# MOTOR_DVR.net
KiCad netlist of a schematic drawn in Altium Designer
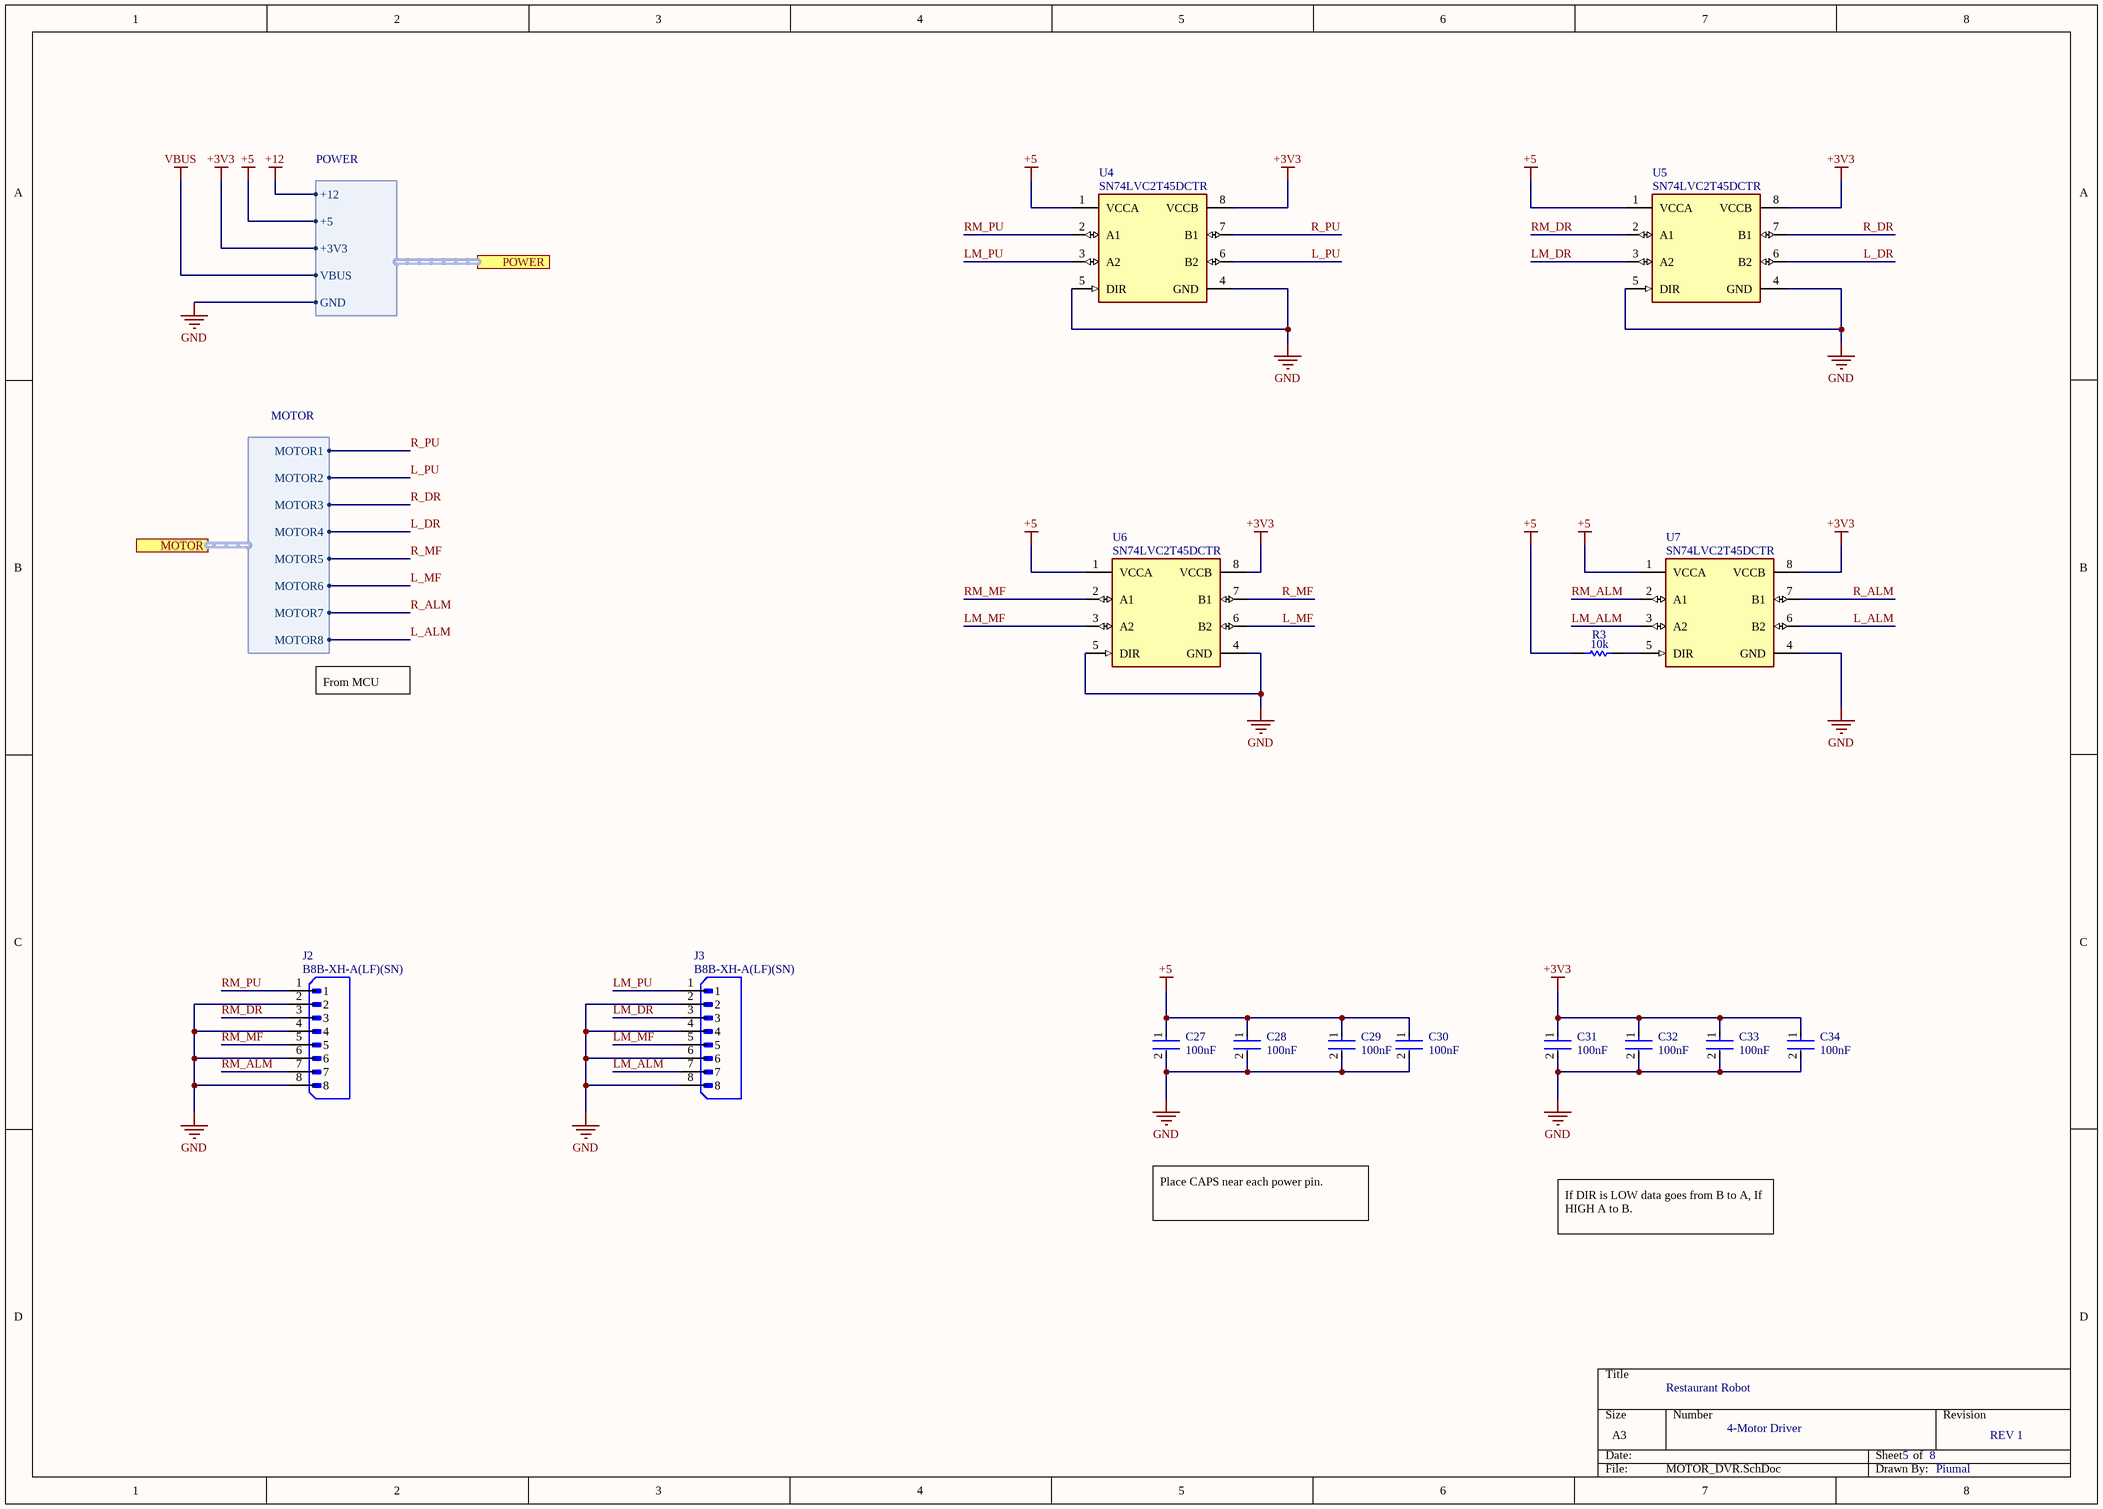
[diagram p0: MOTOR_DVR.SchDoc]

(export (version "E")
  (design (tool "Eeschema 10.0.6"))
  (components
    (comp (ref "C27")
      (value "CL21B104KOANNNC")
      (footprint "FP-CL21-IPC_A")
      (description "CL21 Series 0805 100nF 16V ±10% Tolerance X7R Multilayer Ceramic Chip Capacitor")
      (fields (field (name "TOLERANCE") "10%") (field (name "CAPACITANCE") "100nF"))
      (libsource (lib "Altium Content Vault") (part "b4654b650e69147ec39a6b967a45e02"))
    )
    (comp (ref "C28")
      (value "CL21B104KOANNNC")
      (footprint "FP-CL21-IPC_A")
      (description "CL21 Series 0805 100nF 16V ±10% Tolerance X7R Multilayer Ceramic Chip Capacitor")
      (fields (field (name "TOLERANCE") "10%") (field (name "CAPACITANCE") "100nF"))
      (libsource (lib "Altium Content Vault") (part "b4654b650e69147ec39a6b967a45e02"))
    )
    (comp (ref "C29")
      (value "CL21B104KOANNNC")
      (footprint "FP-CL21-IPC_A")
      (description "CL21 Series 0805 100nF 16V ±10% Tolerance X7R Multilayer Ceramic Chip Capacitor")
      (fields (field (name "TOLERANCE") "10%") (field (name "CAPACITANCE") "100nF"))
      (libsource (lib "Altium Content Vault") (part "b4654b650e69147ec39a6b967a45e02"))
    )
    (comp (ref "C30")
      (value "CL21B104KOANNNC")
      (footprint "FP-CL21-IPC_A")
      (description "CL21 Series 0805 100nF 16V ±10% Tolerance X7R Multilayer Ceramic Chip Capacitor")
      (fields (field (name "TOLERANCE") "10%") (field (name "CAPACITANCE") "100nF"))
      (libsource (lib "Altium Content Vault") (part "b4654b650e69147ec39a6b967a45e02"))
    )
    (comp (ref "C31")
      (value "CL21B104KOANNNC")
      (footprint "FP-CL21-IPC_A")
      (description "CL21 Series 0805 100nF 16V ±10% Tolerance X7R Multilayer Ceramic Chip Capacitor")
      (fields (field (name "TOLERANCE") "10%") (field (name "CAPACITANCE") "100nF"))
      (libsource (lib "Altium Content Vault") (part "b4654b650e69147ec39a6b967a45e02"))
    )
    (comp (ref "C32")
      (value "CL21B104KOANNNC")
      (footprint "FP-CL21-IPC_A")
      (description "CL21 Series 0805 100nF 16V ±10% Tolerance X7R Multilayer Ceramic Chip Capacitor")
      (fields (field (name "TOLERANCE") "10%") (field (name "CAPACITANCE") "100nF"))
      (libsource (lib "Altium Content Vault") (part "b4654b650e69147ec39a6b967a45e02"))
    )
    (comp (ref "C33")
      (value "CL21B104KOANNNC")
      (footprint "FP-CL21-IPC_A")
      (description "CL21 Series 0805 100nF 16V ±10% Tolerance X7R Multilayer Ceramic Chip Capacitor")
      (fields (field (name "TOLERANCE") "10%") (field (name "CAPACITANCE") "100nF"))
      (libsource (lib "Altium Content Vault") (part "b4654b650e69147ec39a6b967a45e02"))
    )
    (comp (ref "C34")
      (value "CL21B104KOANNNC")
      (footprint "FP-CL21-IPC_A")
      (description "CL21 Series 0805 100nF 16V ±10% Tolerance X7R Multilayer Ceramic Chip Capacitor")
      (fields (field (name "TOLERANCE") "10%") (field (name "CAPACITANCE") "100nF"))
      (libsource (lib "Altium Content Vault") (part "b4654b650e69147ec39a6b967a45e02"))
    )
    (comp (ref "J2")
      (value "B8B-XH-A(LF)(SN)")
      (footprint "JST_B8B-XH-A(LF)(SN)")
      (description "Connector Header Through Hole 8 position 0.098 (2.50mm)")
      (fields (field (name "MF") "JST Sales America Inc."))
      (libsource (lib "B8B-XH-A_LF__SN_ (1)") (part "B8B-XH-A(LF)(SN)"))
    )
    (comp (ref "J3")
      (value "B8B-XH-A(LF)(SN)")
      (footprint "JST_B8B-XH-A(LF)(SN)")
      (description "Connector Header Through Hole 8 position 0.098 (2.50mm)")
      (fields (field (name "MF") "JST Sales America Inc."))
      (libsource (lib "B8B-XH-A_LF__SN_ (1)") (part "B8B-XH-A(LF)(SN)"))
    )
    (comp (ref "R3")
      (value "RC0805JR-0710KL")
      (footprint "RESC2013X60X35ML10T20")
      (description "Chip Resistor, 10 KOhm, +/- 5%, 0.125 W, -55 to 155 degC, 0805 (2012 Metric), RoHS, Tape and Reel")
      (fields (field (name "MANUFACTURER") "Yageo") (field (name "RESISTANCE") "10k"))
      (libsource (lib "Altium Content Vault") (part "RES-2"))
    )
    (comp (ref "U4")
      (value "SN74LVC2T45DCTR")
      (footprint "FP-DCT0008A-MFG")
      (description "IC TRNSLTR BIDIRECTIONAL SM8")
      (fields
        (field (name "MANUFACTURER") "Texas Instruments")
        (field (name "OCTOPART") "https://octopart.com/sn74lvc2t45dctr-texas+instruments-517051")
      )
      (libsource (lib "Altium Content Vault") (part "271d40e9c72c712db4b2912206096bb"))
    )
    (comp (ref "U5")
      (value "SN74LVC2T45DCTR")
      (footprint "FP-DCT0008A-MFG")
      (description "IC TRNSLTR BIDIRECTIONAL SM8")
      (fields
        (field (name "MANUFACTURER") "Texas Instruments")
        (field (name "OCTOPART") "https://octopart.com/sn74lvc2t45dctr-texas+instruments-517051")
      )
      (libsource (lib "Altium Content Vault") (part "271d40e9c72c712db4b2912206096bb"))
    )
    (comp (ref "U6")
      (value "SN74LVC2T45DCTR")
      (footprint "FP-DCT0008A-MFG")
      (description "IC TRNSLTR BIDIRECTIONAL SM8")
      (fields
        (field (name "MANUFACTURER") "Texas Instruments")
        (field (name "OCTOPART") "https://octopart.com/sn74lvc2t45dctr-texas+instruments-517051")
      )
      (libsource (lib "Altium Content Vault") (part "271d40e9c72c712db4b2912206096bb"))
    )
    (comp (ref "U7")
      (value "SN74LVC2T45DCTR")
      (footprint "FP-DCT0008A-MFG")
      (description "IC TRNSLTR BIDIRECTIONAL SM8")
      (fields
        (field (name "MANUFACTURER") "Texas Instruments")
        (field (name "OCTOPART") "https://octopart.com/sn74lvc2t45dctr-texas+instruments-517051")
      )
      (libsource (lib "Altium Content Vault") (part "271d40e9c72c712db4b2912206096bb"))
    )
  )
  (nets
    (net (code "3") (name "+3V3") (class "Default")
      (node (ref "C31") (pin "1") (pinfunction "1_1") (pintype "passive"))
      (node (ref "C32") (pin "1") (pinfunction "1_1") (pintype "passive"))
      (node (ref "C33") (pin "1") (pinfunction "1_1") (pintype "passive"))
      (node (ref "C34") (pin "1") (pinfunction "1_1") (pintype "passive"))
      (node (ref "U4") (pin "8") (pinfunction "VCCB_8") (pintype "passive"))
      (node (ref "U5") (pin "8") (pinfunction "VCCB_8") (pintype "passive"))
      (node (ref "U6") (pin "8") (pinfunction "VCCB_8") (pintype "passive"))
      (node (ref "U7") (pin "8") (pinfunction "VCCB_8") (pintype "passive"))
    )
    (net (code "4") (name "+5") (class "Default")
      (node (ref "C27") (pin "1") (pinfunction "1_1") (pintype "passive"))
      (node (ref "C28") (pin "1") (pinfunction "1_1") (pintype "passive"))
      (node (ref "C29") (pin "1") (pinfunction "1_1") (pintype "passive"))
      (node (ref "C30") (pin "1") (pinfunction "1_1") (pintype "passive"))
      (node (ref "R3") (pin "1") (pinfunction "1_1") (pintype "passive"))
      (node (ref "U4") (pin "1") (pinfunction "VCCA_1") (pintype "power_in"))
      (node (ref "U5") (pin "1") (pinfunction "VCCA_1") (pintype "power_in"))
      (node (ref "U6") (pin "1") (pinfunction "VCCA_1") (pintype "power_in"))
      (node (ref "U7") (pin "1") (pinfunction "VCCA_1") (pintype "power_in"))
    )
    (net (code "6") (name "/LM_ALM") (class "Default")
      (node (ref "J3") (pin "7") (pinfunction "7_7") (pintype "passive"))
      (node (ref "U7") (pin "3") (pinfunction "A2_3") (pintype "bidirectional"))
    )
    (net (code "7") (name "/LM_DR") (class "Default")
      (node (ref "J3") (pin "3") (pinfunction "3_3") (pintype "passive"))
      (node (ref "U5") (pin "3") (pinfunction "A2_3") (pintype "bidirectional"))
    )
    (net (code "8") (name "/LM_MF") (class "Default")
      (node (ref "J3") (pin "5") (pinfunction "5_5") (pintype "passive"))
      (node (ref "U6") (pin "3") (pinfunction "A2_3") (pintype "bidirectional"))
    )
    (net (code "9") (name "/LM_PU") (class "Default")
      (node (ref "J3") (pin "1") (pinfunction "1_1") (pintype "passive"))
      (node (ref "U4") (pin "3") (pinfunction "A2_3") (pintype "bidirectional"))
    )
    (net (code "10") (name "/L_ALM") (class "Default")
      (node (ref "U7") (pin "6") (pinfunction "B2_6") (pintype "bidirectional"))
    )
    (net (code "11") (name "/L_DR") (class "Default")
      (node (ref "U5") (pin "6") (pinfunction "B2_6") (pintype "bidirectional"))
    )
    (net (code "12") (name "/L_MF") (class "Default")
      (node (ref "U6") (pin "6") (pinfunction "B2_6") (pintype "bidirectional"))
    )
    (net (code "13") (name "/L_PU") (class "Default")
      (node (ref "U4") (pin "6") (pinfunction "B2_6") (pintype "bidirectional"))
    )
    (net (code "14") (name "/RM_ALM") (class "Default")
      (node (ref "J2") (pin "7") (pinfunction "7_7") (pintype "passive"))
      (node (ref "U7") (pin "2") (pinfunction "A1_2") (pintype "bidirectional"))
    )
    (net (code "15") (name "/RM_DR") (class "Default")
      (node (ref "J2") (pin "3") (pinfunction "3_3") (pintype "passive"))
      (node (ref "U5") (pin "2") (pinfunction "A1_2") (pintype "bidirectional"))
    )
    (net (code "16") (name "/RM_MF") (class "Default")
      (node (ref "J2") (pin "5") (pinfunction "5_5") (pintype "passive"))
      (node (ref "U6") (pin "2") (pinfunction "A1_2") (pintype "bidirectional"))
    )
    (net (code "17") (name "/RM_PU") (class "Default")
      (node (ref "J2") (pin "1") (pinfunction "1_1") (pintype "passive"))
      (node (ref "U4") (pin "2") (pinfunction "A1_2") (pintype "bidirectional"))
    )
    (net (code "18") (name "/R_ALM") (class "Default")
      (node (ref "U7") (pin "7") (pinfunction "B1_7") (pintype "bidirectional"))
    )
    (net (code "19") (name "/R_DR") (class "Default")
      (node (ref "U5") (pin "7") (pinfunction "B1_7") (pintype "bidirectional"))
    )
    (net (code "20") (name "/R_MF") (class "Default")
      (node (ref "U6") (pin "7") (pinfunction "B1_7") (pintype "bidirectional"))
    )
    (net (code "21") (name "/R_PU") (class "Default")
      (node (ref "U4") (pin "7") (pinfunction "B1_7") (pintype "bidirectional"))
    )
    (net (code "24") (name "GND") (class "Default")
      (node (ref "C27") (pin "2") (pinfunction "2_2") (pintype "passive"))
      (node (ref "C28") (pin "2") (pinfunction "2_2") (pintype "passive"))
      (node (ref "C29") (pin "2") (pinfunction "2_2") (pintype "passive"))
      (node (ref "C30") (pin "2") (pinfunction "2_2") (pintype "passive"))
      (node (ref "C31") (pin "2") (pinfunction "2_2") (pintype "passive"))
      (node (ref "C32") (pin "2") (pinfunction "2_2") (pintype "passive"))
      (node (ref "C33") (pin "2") (pinfunction "2_2") (pintype "passive"))
      (node (ref "C34") (pin "2") (pinfunction "2_2") (pintype "passive"))
      (node (ref "J2") (pin "2") (pinfunction "2_2") (pintype "passive"))
      (node (ref "J2") (pin "4") (pinfunction "4_4") (pintype "passive"))
      (node (ref "J2") (pin "6") (pinfunction "6_6") (pintype "passive"))
      (node (ref "J2") (pin "8") (pinfunction "8_8") (pintype "passive"))
      (node (ref "J3") (pin "2") (pinfunction "2_2") (pintype "passive"))
      (node (ref "J3") (pin "4") (pinfunction "4_4") (pintype "passive"))
      (node (ref "J3") (pin "6") (pinfunction "6_6") (pintype "passive"))
      (node (ref "J3") (pin "8") (pinfunction "8_8") (pintype "passive"))
      (node (ref "U4") (pin "4") (pinfunction "GND_4") (pintype "power_in"))
      (node (ref "U4") (pin "5") (pinfunction "DIR_5") (pintype "input"))
      (node (ref "U5") (pin "4") (pinfunction "GND_4") (pintype "power_in"))
      (node (ref "U5") (pin "5") (pinfunction "DIR_5") (pintype "input"))
      (node (ref "U6") (pin "4") (pinfunction "GND_4") (pintype "power_in"))
      (node (ref "U6") (pin "5") (pinfunction "DIR_5") (pintype "input"))
      (node (ref "U7") (pin "4") (pinfunction "GND_4") (pintype "power_in"))
    )
    (net (code "25") (name "Net-(U7-DIR)") (class "Default")
      (node (ref "R3") (pin "2") (pinfunction "2_2") (pintype "passive"))
      (node (ref "U7") (pin "5") (pinfunction "DIR_5") (pintype "input"))
    )
  )
)
